# Schematic_v2.net
KiCad netlist of a schematic drawn in EAGLE
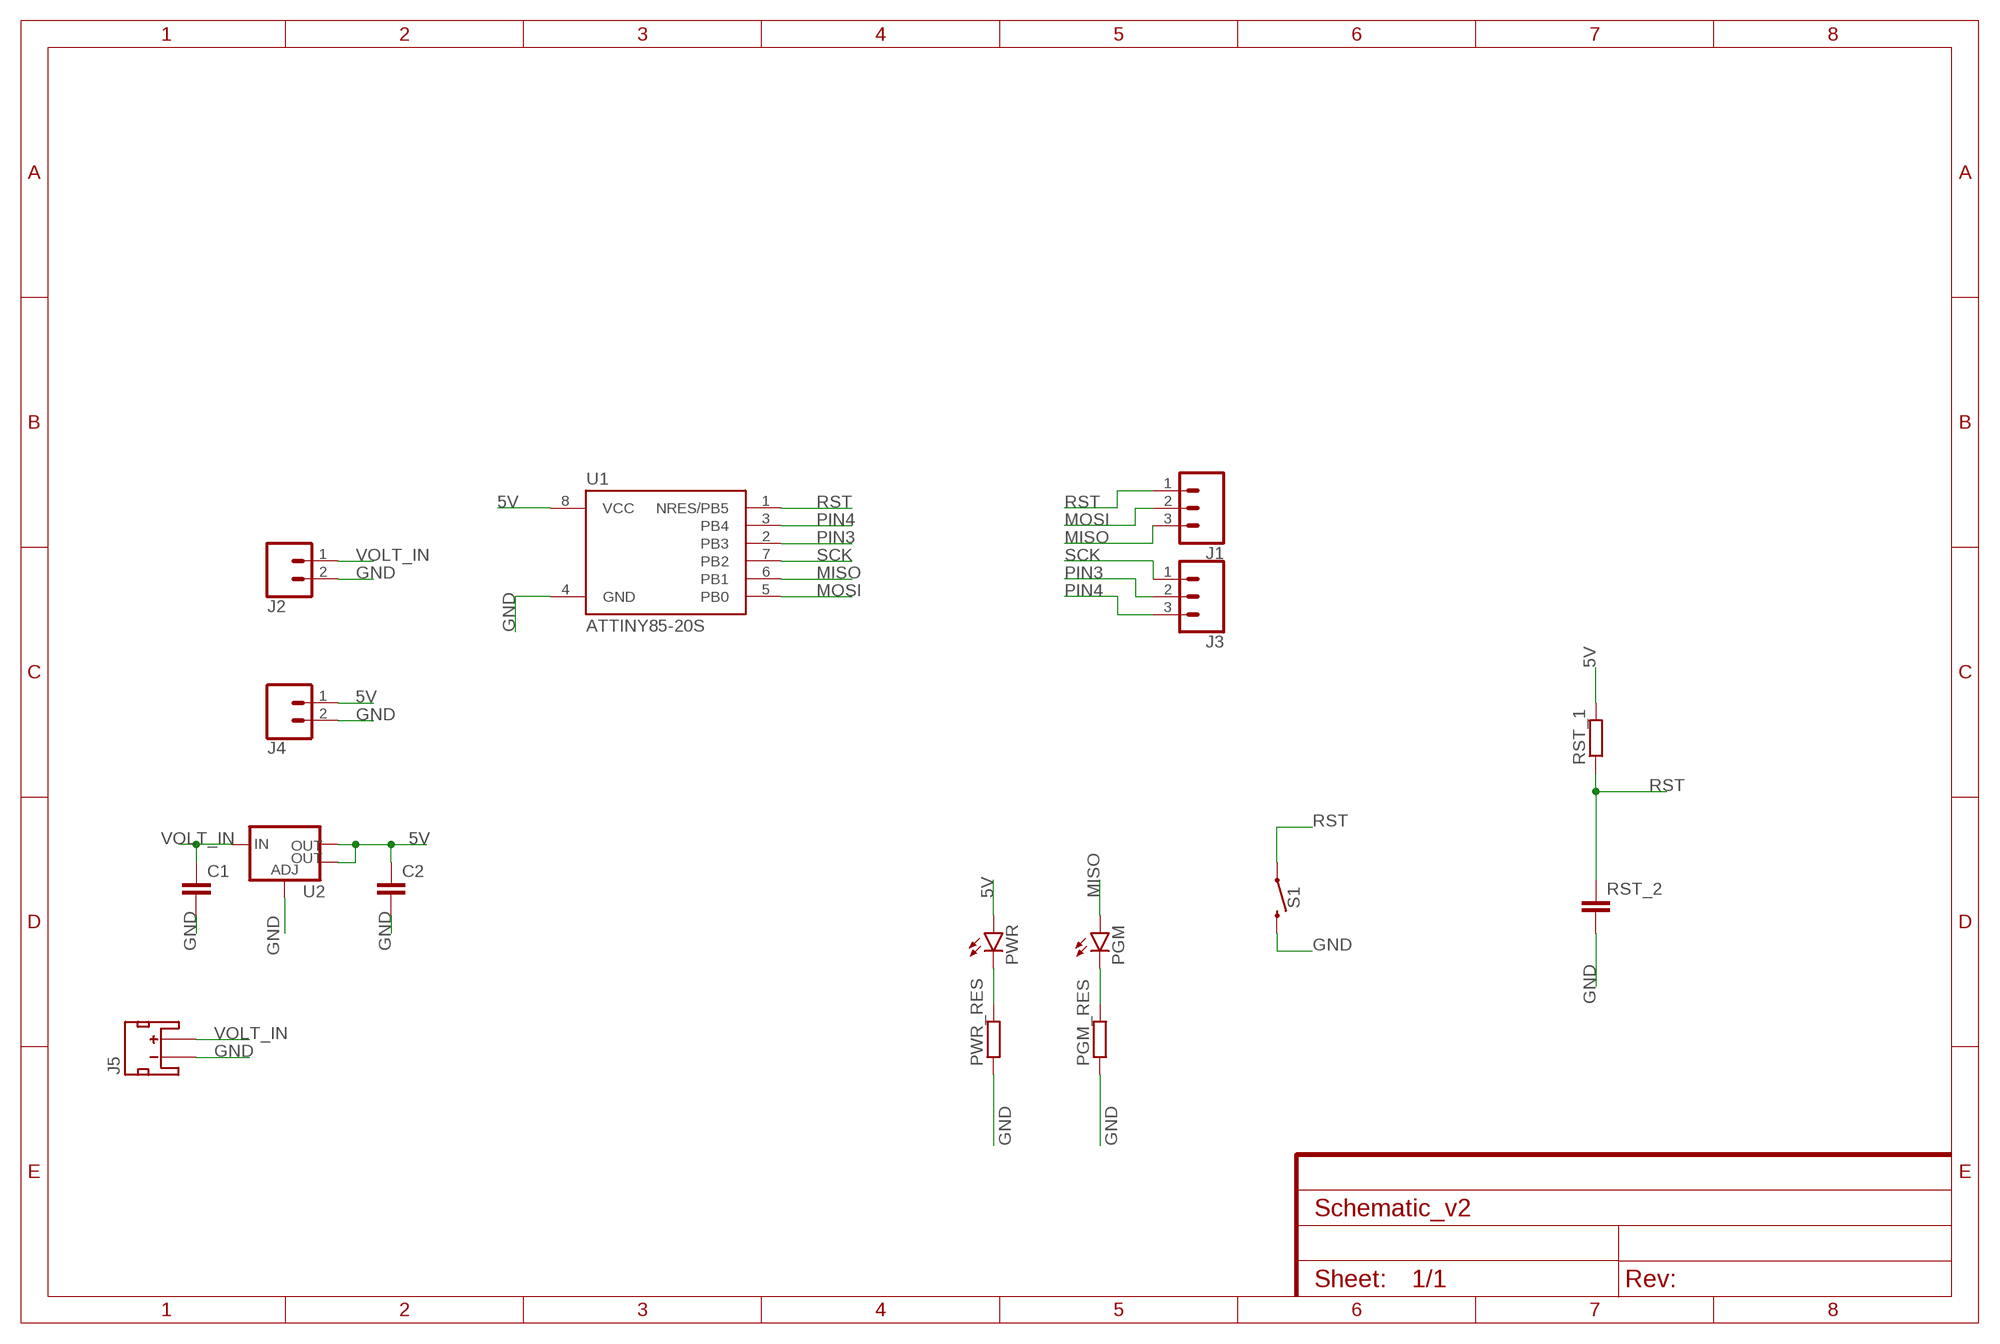
[diagram p0: schematic, sheet 1]

(export (version "E")
  (design (tool "Eeschema 10.0.6"))
  (components
    (comp (ref "C1")
      (value "C-EUC0805")
      (footprint "eagle-import:C0805")
      (libsource (lib "eagle-import") (part "C-EUC0805"))
    )
    (comp (ref "C2")
      (value "C-EUC0805")
      (footprint "eagle-import:C0805")
      (libsource (lib "eagle-import") (part "C-EUC0805"))
    )
    (comp (ref "J1")
      (value "CONN_031X03_NO_SILK")
      (footprint "eagle-import:1X03_NO_SILK")
      (libsource (lib "eagle-import") (part "CONN_031X03_NO_SILK"))
    )
    (comp (ref "J2")
      (value "CONN_021X02_NO_SILK")
      (footprint "eagle-import:1X02_NO_SILK")
      (libsource (lib "eagle-import") (part "CONN_021X02_NO_SILK"))
    )
    (comp (ref "J3")
      (value "CONN_031X03_NO_SILK")
      (footprint "eagle-import:1X03_NO_SILK")
      (libsource (lib "eagle-import") (part "CONN_031X03_NO_SILK"))
    )
    (comp (ref "J4")
      (value "CONN_021X02_NO_SILK")
      (footprint "eagle-import:1X02_NO_SILK")
      (libsource (lib "eagle-import") (part "CONN_021X02_NO_SILK"))
    )
    (comp (ref "J5")
      (value "JST_2MM_MALE")
      (footprint "eagle-import:JST-2-SMD")
      (libsource (lib "eagle-import") (part "JST_2MM_MALE"))
    )
    (comp (ref "PGM")
      (value "LEDSML0805")
      (footprint "eagle-import:SML0805")
      (libsource (lib "eagle-import") (part "LEDSML0805"))
    )
    (comp (ref "PGM_RES")
      (value "R-EU_R0805")
      (footprint "eagle-import:R0805")
      (libsource (lib "eagle-import") (part "R-EU_R0805"))
    )
    (comp (ref "PWR")
      (value "LEDSML0805")
      (footprint "eagle-import:SML0805")
      (libsource (lib "eagle-import") (part "LEDSML0805"))
    )
    (comp (ref "PWR_RES")
      (value "R-EU_R0805")
      (footprint "eagle-import:R0805")
      (libsource (lib "eagle-import") (part "R-EU_R0805"))
    )
    (comp (ref "RST_1")
      (value "R-EU_R0805")
      (footprint "eagle-import:R0805")
      (libsource (lib "eagle-import") (part "R-EU_R0805"))
    )
    (comp (ref "RST_2")
      (value "C-EUC0805")
      (footprint "eagle-import:C0805")
      (libsource (lib "eagle-import") (part "C-EUC0805"))
    )
    (comp (ref "S1")
      (value "MOMENTARY-SWITCH-SPST-SMD-6.0X3.5MM")
      (footprint "eagle-import:TACTILE_SWITCH_SMD_6.0X3.5MM")
      (libsource (lib "eagle-import") (part "MOMENTARY-SWITCH-SPST-SMD-6.0X3.5MM"))
    )
    (comp (ref "U1")
      (value "ATTINY85-20S")
      (footprint "eagle-import:SOIC8_EIAJ_208MIL")
      (libsource (lib "eagle-import") (part "ATTINY85S-20"))
    )
    (comp (ref "U2")
      (value "V_REG_LM1117SOT223")
      (footprint "eagle-import:SOT223")
      (libsource (lib "eagle-import") (part "V_REG_LM1117SOT223"))
    )
  )
  (nets
    (net (code "1") (name "/5V") (class "Default")
      (node (ref "C2") (pin "1") (pinfunction "1_1") (pintype "passive"))
      (node (ref "J4") (pin "1") (pinfunction "1_1") (pintype "passive"))
      (node (ref "PWR") (pin "A") (pinfunction "A_A") (pintype "passive"))
      (node (ref "RST_1") (pin "2") (pinfunction "2_2") (pintype "passive"))
      (node (ref "U1") (pin "8") (pinfunction "VCC_8") (pintype "power_in"))
      (node (ref "U2") (pin "2") (pinfunction "OUT_2") (pintype "output"))
      (node (ref "U2") (pin "4") (pinfunction "OUT_4") (pintype "output"))
    )
    (net (code "2") (name "/GND") (class "Default")
      (node (ref "C1") (pin "2") (pinfunction "2_2") (pintype "passive"))
      (node (ref "C2") (pin "2") (pinfunction "2_2") (pintype "passive"))
      (node (ref "J2") (pin "2") (pinfunction "2_2") (pintype "passive"))
      (node (ref "J4") (pin "2") (pinfunction "2_2") (pintype "passive"))
      (node (ref "J5") (pin "1") (pinfunction "-_1") (pintype "bidirectional"))
      (node (ref "PGM_RES") (pin "1") (pinfunction "1_1") (pintype "passive"))
      (node (ref "PWR_RES") (pin "1") (pinfunction "1_1") (pintype "passive"))
      (node (ref "RST_2") (pin "2") (pinfunction "2_2") (pintype "passive"))
      (node (ref "S1") (pin "2") (pinfunction "2_2") (pintype "passive"))
      (node (ref "U1") (pin "4") (pinfunction "GND_4") (pintype "power_in"))
      (node (ref "U2") (pin "1") (pinfunction "ADJ_1") (pintype "input"))
    )
    (net (code "3") (name "/MISO") (class "Default")
      (node (ref "J1") (pin "3") (pinfunction "3_3") (pintype "passive"))
      (node (ref "PGM") (pin "A") (pinfunction "A_A") (pintype "passive"))
      (node (ref "U1") (pin "6") (pinfunction "PB1_6") (pintype "bidirectional"))
    )
    (net (code "4") (name "/MOSI") (class "Default")
      (node (ref "J1") (pin "2") (pinfunction "2_2") (pintype "passive"))
      (node (ref "U1") (pin "5") (pinfunction "PB0_5") (pintype "bidirectional"))
    )
    (net (code "5") (name "/PIN3") (class "Default")
      (node (ref "J3") (pin "2") (pinfunction "2_2") (pintype "passive"))
      (node (ref "U1") (pin "2") (pinfunction "PB3_2") (pintype "bidirectional"))
    )
    (net (code "6") (name "/PIN4") (class "Default")
      (node (ref "J3") (pin "3") (pinfunction "3_3") (pintype "passive"))
      (node (ref "U1") (pin "3") (pinfunction "PB4_3") (pintype "bidirectional"))
    )
    (net (code "7") (name "/RST") (class "Default")
      (node (ref "J1") (pin "1") (pinfunction "1_1") (pintype "passive"))
      (node (ref "RST_1") (pin "1") (pinfunction "1_1") (pintype "passive"))
      (node (ref "RST_2") (pin "1") (pinfunction "1_1") (pintype "passive"))
      (node (ref "S1") (pin "1") (pinfunction "1_1") (pintype "passive"))
      (node (ref "U1") (pin "1") (pinfunction "NRES/PB5_1") (pintype "bidirectional"))
    )
    (net (code "8") (name "/SCK") (class "Default")
      (node (ref "J3") (pin "1") (pinfunction "1_1") (pintype "passive"))
      (node (ref "U1") (pin "7") (pinfunction "PB2_7") (pintype "bidirectional"))
    )
    (net (code "9") (name "/VOLT_IN") (class "Default")
      (node (ref "C1") (pin "1") (pinfunction "1_1") (pintype "passive"))
      (node (ref "J2") (pin "1") (pinfunction "1_1") (pintype "passive"))
      (node (ref "J5") (pin "2") (pinfunction "+_2") (pintype "bidirectional"))
      (node (ref "U2") (pin "3") (pinfunction "IN_3") (pintype "input"))
    )
    (net (code "10") (name "Net-(PGM-PadC)") (class "Default")
      (node (ref "PGM") (pin "C") (pinfunction "C_C") (pintype "passive"))
      (node (ref "PGM_RES") (pin "2") (pinfunction "2_2") (pintype "passive"))
    )
    (net (code "11") (name "Net-(PWR-PadC)") (class "Default")
      (node (ref "PWR") (pin "C") (pinfunction "C_C") (pintype "passive"))
      (node (ref "PWR_RES") (pin "2") (pinfunction "2_2") (pintype "passive"))
    )
    (net (code "12") (name "unconnected-(J5-PAD1-PadNC1)") (class "Default")
      (node (ref "J5") (pin "NC1") (pinfunction "PAD1_NC1") (pintype "bidirectional"))
    )
    (net (code "13") (name "unconnected-(J5-PAD2-PadNC2)") (class "Default")
      (node (ref "J5") (pin "NC2") (pinfunction "PAD2_NC2") (pintype "bidirectional"))
    )
  )
)
